# fpga.net
KiCad netlist of a schematic drawn in Altium Designer
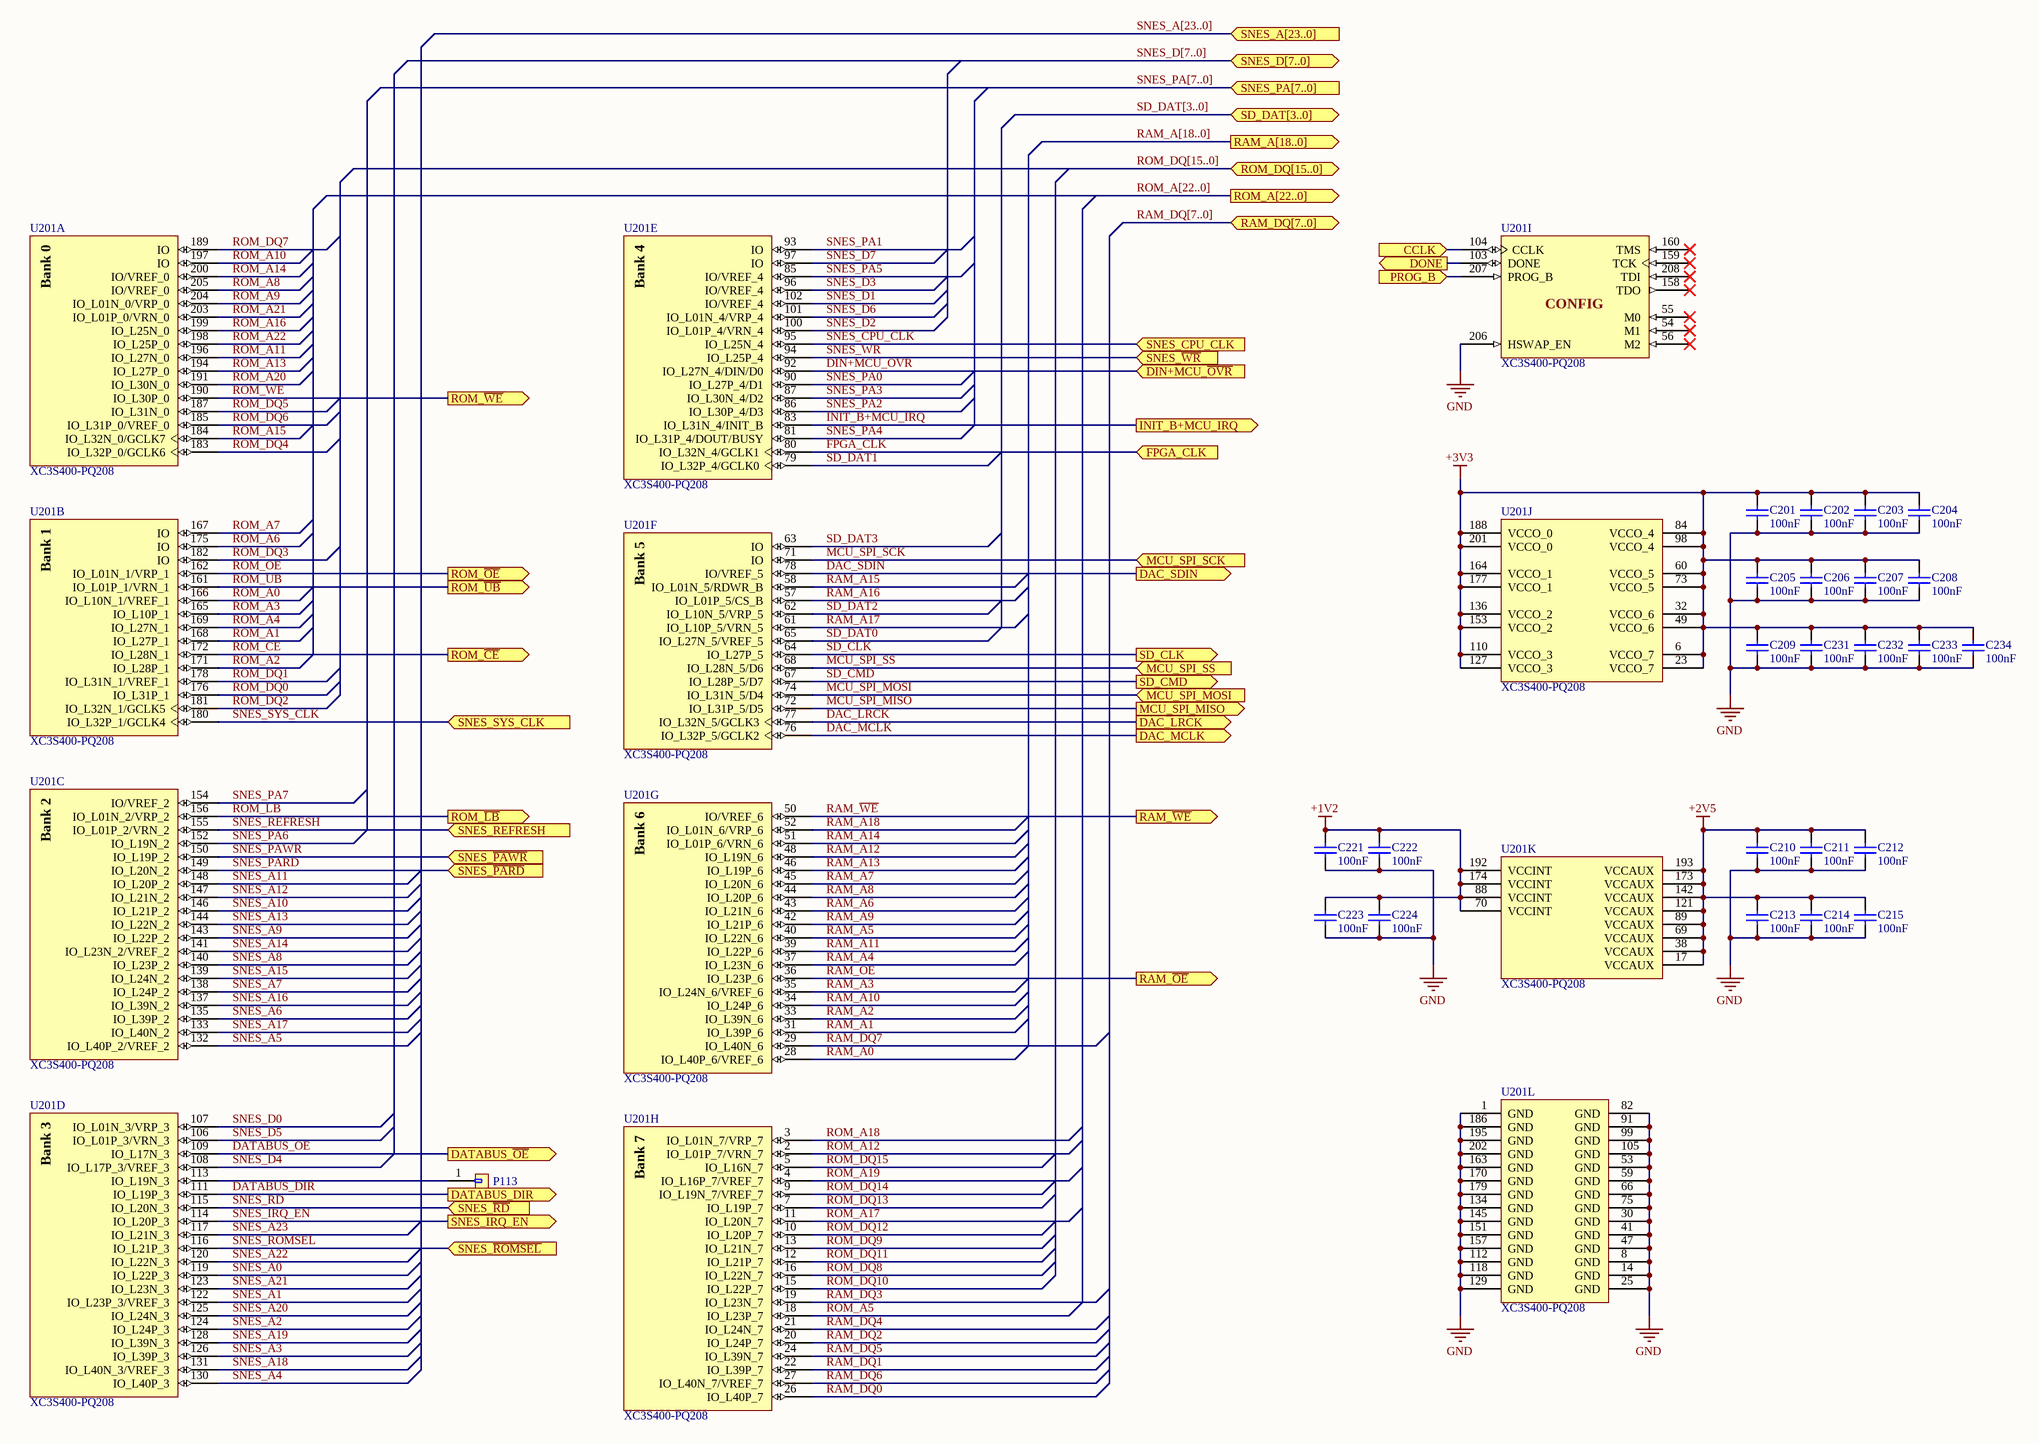
[diagram p0: fpga.SchDoc]

(export (version "E")
  (design (tool "Eeschema 10.0.6"))
  (components
    (comp (ref "C201")
      (value "100nF")
      (footprint "SM0805")
      (description "Capacitor")
      (libsource (lib "Miscellaneous Devices") (part "Cap"))
    )
    (comp (ref "C202")
      (value "100nF")
      (footprint "SM0805")
      (description "Capacitor")
      (libsource (lib "Miscellaneous Devices") (part "Cap"))
    )
    (comp (ref "C203")
      (value "100nF")
      (footprint "SM0805")
      (description "Capacitor")
      (libsource (lib "Miscellaneous Devices") (part "Cap"))
    )
    (comp (ref "C204")
      (value "100nF")
      (footprint "SM0805")
      (description "Capacitor")
      (libsource (lib "Miscellaneous Devices") (part "Cap"))
    )
    (comp (ref "C205")
      (value "100nF")
      (footprint "SM0805")
      (description "Capacitor")
      (libsource (lib "Miscellaneous Devices") (part "Cap"))
    )
    (comp (ref "C206")
      (value "100nF")
      (footprint "SM0805")
      (description "Capacitor")
      (libsource (lib "Miscellaneous Devices") (part "Cap"))
    )
    (comp (ref "C207")
      (value "100nF")
      (footprint "SM0805")
      (description "Capacitor")
      (libsource (lib "Miscellaneous Devices") (part "Cap"))
    )
    (comp (ref "C208")
      (value "100nF")
      (footprint "SM0805")
      (description "Capacitor")
      (libsource (lib "Miscellaneous Devices") (part "Cap"))
    )
    (comp (ref "C209")
      (value "100nF")
      (footprint "SM0805")
      (description "Capacitor")
      (libsource (lib "Miscellaneous Devices") (part "Cap"))
    )
    (comp (ref "C210")
      (value "100nF")
      (footprint "SM0805")
      (description "Capacitor")
      (libsource (lib "Miscellaneous Devices") (part "Cap"))
    )
    (comp (ref "C211")
      (value "100nF")
      (footprint "SM0805")
      (description "Capacitor")
      (libsource (lib "Miscellaneous Devices") (part "Cap"))
    )
    (comp (ref "C212")
      (value "100nF")
      (footprint "SM0805")
      (description "Capacitor")
      (libsource (lib "Miscellaneous Devices") (part "Cap"))
    )
    (comp (ref "C213")
      (value "100nF")
      (footprint "SM0805")
      (description "Capacitor")
      (libsource (lib "Miscellaneous Devices") (part "Cap"))
    )
    (comp (ref "C214")
      (value "100nF")
      (footprint "SM0805")
      (description "Capacitor")
      (libsource (lib "Miscellaneous Devices") (part "Cap"))
    )
    (comp (ref "C215")
      (value "100nF")
      (footprint "SM0805")
      (description "Capacitor")
      (libsource (lib "Miscellaneous Devices") (part "Cap"))
    )
    (comp (ref "C221")
      (value "100nF")
      (footprint "SM0805")
      (description "Capacitor")
      (libsource (lib "Miscellaneous Devices") (part "Cap"))
    )
    (comp (ref "C222")
      (value "100nF")
      (footprint "SM0805")
      (description "Capacitor")
      (libsource (lib "Miscellaneous Devices") (part "Cap"))
    )
    (comp (ref "C223")
      (value "100nF")
      (footprint "SM0805")
      (description "Capacitor")
      (libsource (lib "Miscellaneous Devices") (part "Cap"))
    )
    (comp (ref "C224")
      (value "100nF")
      (footprint "SM0805")
      (description "Capacitor")
      (libsource (lib "Miscellaneous Devices") (part "Cap"))
    )
    (comp (ref "C231")
      (value "100nF")
      (footprint "SM0805")
      (description "Capacitor")
      (libsource (lib "Miscellaneous Devices") (part "Cap"))
    )
    (comp (ref "C232")
      (value "100nF")
      (footprint "SM0805")
      (description "Capacitor")
      (libsource (lib "Miscellaneous Devices") (part "Cap"))
    )
    (comp (ref "C233")
      (value "100nF")
      (footprint "SM0805")
      (description "Capacitor")
      (libsource (lib "Miscellaneous Devices") (part "Cap"))
    )
    (comp (ref "C234")
      (value "100nF")
      (footprint "SM0805")
      (description "Capacitor")
      (libsource (lib "Miscellaneous Devices") (part "Cap"))
    )
    (comp (ref "P113") (value "CONN_1") (footprint "CONN_1") (libsource (lib "Schlib1") (part "CONN_1")))
    (comp (ref "U201")
      (value "XC3S400-PQ208")
      (footprint "PQFP208")
      (libsource (lib "Schlib1") (part "XC3S400-PQ208"))
    )
  )
  (nets
    (net (code "1") (name "+1V2") (class "Default")
      (node (ref "C221") (pin "1") (pinfunction "1_1") (pintype "passive"))
      (node (ref "C222") (pin "1") (pinfunction "1_1") (pintype "passive"))
      (node (ref "C223") (pin "1") (pinfunction "1_1") (pintype "passive"))
      (node (ref "C224") (pin "1") (pinfunction "1_1") (pintype "passive"))
      (node (ref "U201") (pin "174") (pinfunction "VCCINT_174") (pintype "power_in"))
      (node (ref "U201") (pin "192") (pinfunction "VCCINT_192") (pintype "power_in"))
      (node (ref "U201") (pin "70") (pinfunction "VCCINT_70") (pintype "power_in"))
      (node (ref "U201") (pin "88") (pinfunction "VCCINT_88") (pintype "power_in"))
    )
    (net (code "2") (name "+2V5") (class "Default")
      (node (ref "C210") (pin "1") (pinfunction "1_1") (pintype "passive"))
      (node (ref "C211") (pin "1") (pinfunction "1_1") (pintype "passive"))
      (node (ref "C212") (pin "1") (pinfunction "1_1") (pintype "passive"))
      (node (ref "C213") (pin "1") (pinfunction "1_1") (pintype "passive"))
      (node (ref "C214") (pin "1") (pinfunction "1_1") (pintype "passive"))
      (node (ref "C215") (pin "1") (pinfunction "1_1") (pintype "passive"))
      (node (ref "U201") (pin "121") (pinfunction "VCCAUX_121") (pintype "power_in"))
      (node (ref "U201") (pin "142") (pinfunction "VCCAUX_142") (pintype "power_in"))
      (node (ref "U201") (pin "17") (pinfunction "VCCAUX_17") (pintype "power_in"))
      (node (ref "U201") (pin "173") (pinfunction "VCCAUX_173") (pintype "power_in"))
      (node (ref "U201") (pin "193") (pinfunction "VCCAUX_193") (pintype "power_in"))
      (node (ref "U201") (pin "38") (pinfunction "VCCAUX_38") (pintype "power_in"))
      (node (ref "U201") (pin "69") (pinfunction "VCCAUX_69") (pintype "power_in"))
      (node (ref "U201") (pin "89") (pinfunction "VCCAUX_89") (pintype "power_in"))
    )
    (net (code "3") (name "+3V3") (class "Default")
      (node (ref "C201") (pin "1") (pinfunction "1_1") (pintype "passive"))
      (node (ref "C202") (pin "1") (pinfunction "1_1") (pintype "passive"))
      (node (ref "C203") (pin "1") (pinfunction "1_1") (pintype "passive"))
      (node (ref "C204") (pin "1") (pinfunction "1_1") (pintype "passive"))
      (node (ref "C205") (pin "1") (pinfunction "1_1") (pintype "passive"))
      (node (ref "C206") (pin "1") (pinfunction "1_1") (pintype "passive"))
      (node (ref "C207") (pin "1") (pinfunction "1_1") (pintype "passive"))
      (node (ref "C208") (pin "1") (pinfunction "1_1") (pintype "passive"))
      (node (ref "C209") (pin "1") (pinfunction "1_1") (pintype "passive"))
      (node (ref "C231") (pin "1") (pinfunction "1_1") (pintype "passive"))
      (node (ref "C232") (pin "1") (pinfunction "1_1") (pintype "passive"))
      (node (ref "C233") (pin "1") (pinfunction "1_1") (pintype "passive"))
      (node (ref "C234") (pin "1") (pinfunction "1_1") (pintype "passive"))
      (node (ref "U201") (pin "110") (pinfunction "VCCO_3_110") (pintype "power_in"))
      (node (ref "U201") (pin "127") (pinfunction "VCCO_3_127") (pintype "power_in"))
      (node (ref "U201") (pin "136") (pinfunction "VCCO_2_136") (pintype "power_in"))
      (node (ref "U201") (pin "153") (pinfunction "VCCO_2_153") (pintype "power_in"))
      (node (ref "U201") (pin "164") (pinfunction "VCCO_1_164") (pintype "power_in"))
      (node (ref "U201") (pin "177") (pinfunction "VCCO_1_177") (pintype "power_in"))
      (node (ref "U201") (pin "188") (pinfunction "VCCO_0_188") (pintype "power_in"))
      (node (ref "U201") (pin "201") (pinfunction "VCCO_0_201") (pintype "power_in"))
      (node (ref "U201") (pin "23") (pinfunction "VCCO_7_23") (pintype "power_in"))
      (node (ref "U201") (pin "32") (pinfunction "VCCO_6_32") (pintype "power_in"))
      (node (ref "U201") (pin "49") (pinfunction "VCCO_6_49") (pintype "power_in"))
      (node (ref "U201") (pin "6") (pinfunction "VCCO_7_6") (pintype "power_in"))
      (node (ref "U201") (pin "60") (pinfunction "VCCO_5_60") (pintype "power_in"))
      (node (ref "U201") (pin "73") (pinfunction "VCCO_5_73") (pintype "power_in"))
      (node (ref "U201") (pin "84") (pinfunction "VCCO_4_84") (pintype "power_in"))
      (node (ref "U201") (pin "98") (pinfunction "VCCO_4_98") (pintype "power_in"))
    )
    (net (code "4") (name "/CCLK") (class "Default")
      (node (ref "U201") (pin "104") (pinfunction "CCLK_104") (pintype "bidirectional"))
    )
    (net (code "5") (name "/DAC_LRCK") (class "Default")
      (node (ref "U201") (pin "77") (pinfunction "IO_L32N_5/GCLK3_77") (pintype "bidirectional"))
    )
    (net (code "6") (name "/DAC_MCLK") (class "Default")
      (node (ref "U201") (pin "76") (pinfunction "IO_L32P_5/GCLK2_76") (pintype "bidirectional"))
    )
    (net (code "7") (name "/DAC_SDIN") (class "Default")
      (node (ref "U201") (pin "78") (pinfunction "IO/VREF_5_78") (pintype "bidirectional"))
    )
    (net (code "8") (name "/DATABUS_DIR") (class "Default")
      (node (ref "U201") (pin "111") (pinfunction "IO_L19P_3_111") (pintype "bidirectional"))
    )
    (net (code "9") (name "/DATABUS_~{OE}") (class "Default")
      (node (ref "U201") (pin "109") (pinfunction "IO_L17N_3_109") (pintype "bidirectional"))
    )
    (net (code "10") (name "/DIN+MCU_~{OVR}") (class "Default")
      (node (ref "U201") (pin "92") (pinfunction "IO_L27N_4/DIN/D0_92") (pintype "bidirectional"))
    )
    (net (code "11") (name "/DONE") (class "Default")
      (node (ref "U201") (pin "103") (pinfunction "DONE_103") (pintype "bidirectional"))
    )
    (net (code "12") (name "/FPGA_CLK") (class "Default")
      (node (ref "U201") (pin "80") (pinfunction "IO_L32N_4/GCLK1_80") (pintype "bidirectional"))
    )
    (net (code "13") (name "/INIT_B+MCU_IRQ") (class "Default")
      (node (ref "U201") (pin "83") (pinfunction "IO_L31N_4/INIT_B_83") (pintype "bidirectional"))
    )
    (net (code "14") (name "/MCU_SPI_MISO") (class "Default")
      (node (ref "U201") (pin "72") (pinfunction "IO_L31P_5/D5_72") (pintype "bidirectional"))
    )
    (net (code "15") (name "/MCU_SPI_MOSI") (class "Default")
      (node (ref "U201") (pin "74") (pinfunction "IO_L31N_5/D4_74") (pintype "bidirectional"))
    )
    (net (code "16") (name "/MCU_SPI_SCK") (class "Default")
      (node (ref "U201") (pin "71") (pinfunction "IO_71") (pintype "bidirectional"))
    )
    (net (code "17") (name "/MCU_SPI_SS") (class "Default")
      (node (ref "U201") (pin "68") (pinfunction "IO_L28N_5/D6_68") (pintype "bidirectional"))
    )
    (net (code "18") (name "/PROG_B") (class "Default")
      (node (ref "U201") (pin "207") (pinfunction "PROG_B_207") (pintype "input"))
    )
    (net (code "19") (name "/RAM_A0") (class "Default")
      (node (ref "U201") (pin "28") (pinfunction "IO_L40P_6/VREF_6_28") (pintype "bidirectional"))
    )
    (net (code "20") (name "/RAM_A1") (class "Default")
      (node (ref "U201") (pin "31") (pinfunction "IO_L39P_6_31") (pintype "bidirectional"))
    )
    (net (code "21") (name "/RAM_A2") (class "Default")
      (node (ref "U201") (pin "33") (pinfunction "IO_L39N_6_33") (pintype "bidirectional"))
    )
    (net (code "22") (name "/RAM_A3") (class "Default")
      (node (ref "U201") (pin "35") (pinfunction "IO_L24N_6/VREF_6_35") (pintype "bidirectional"))
    )
    (net (code "23") (name "/RAM_A4") (class "Default")
      (node (ref "U201") (pin "37") (pinfunction "IO_L23N_6_37") (pintype "bidirectional"))
    )
    (net (code "24") (name "/RAM_A5") (class "Default")
      (node (ref "U201") (pin "40") (pinfunction "IO_L22N_6_40") (pintype "bidirectional"))
    )
    (net (code "25") (name "/RAM_A6") (class "Default")
      (node (ref "U201") (pin "43") (pinfunction "IO_L21N_6_43") (pintype "bidirectional"))
    )
    (net (code "26") (name "/RAM_A7") (class "Default")
      (node (ref "U201") (pin "45") (pinfunction "IO_L20N_6_45") (pintype "bidirectional"))
    )
    (net (code "27") (name "/RAM_A8") (class "Default")
      (node (ref "U201") (pin "44") (pinfunction "IO_L20P_6_44") (pintype "bidirectional"))
    )
    (net (code "28") (name "/RAM_A9") (class "Default")
      (node (ref "U201") (pin "42") (pinfunction "IO_L21P_6_42") (pintype "bidirectional"))
    )
    (net (code "29") (name "/RAM_A10") (class "Default")
      (node (ref "U201") (pin "34") (pinfunction "IO_L24P_6_34") (pintype "bidirectional"))
    )
    (net (code "30") (name "/RAM_A11") (class "Default")
      (node (ref "U201") (pin "39") (pinfunction "IO_L22P_6_39") (pintype "bidirectional"))
    )
    (net (code "31") (name "/RAM_A12") (class "Default")
      (node (ref "U201") (pin "48") (pinfunction "IO_L19N_6_48") (pintype "bidirectional"))
    )
    (net (code "32") (name "/RAM_A13") (class "Default")
      (node (ref "U201") (pin "46") (pinfunction "IO_L19P_6_46") (pintype "bidirectional"))
    )
    (net (code "33") (name "/RAM_A14") (class "Default")
      (node (ref "U201") (pin "51") (pinfunction "IO_L01P_6/VRN_6_51") (pintype "bidirectional"))
    )
    (net (code "34") (name "/RAM_A15") (class "Default")
      (node (ref "U201") (pin "58") (pinfunction "IO_L01N_5/RDWR_B_58") (pintype "bidirectional"))
    )
    (net (code "35") (name "/RAM_A16") (class "Default")
      (node (ref "U201") (pin "57") (pinfunction "IO_L01P_5/CS_B_57") (pintype "bidirectional"))
    )
    (net (code "36") (name "/RAM_A17") (class "Default")
      (node (ref "U201") (pin "61") (pinfunction "IO_L10P_5/VRN_5_61") (pintype "bidirectional"))
    )
    (net (code "37") (name "/RAM_A18") (class "Default")
      (node (ref "U201") (pin "52") (pinfunction "IO_L01N_6/VRP_6_52") (pintype "bidirectional"))
    )
    (net (code "39") (name "/RAM_DQ0") (class "Default")
      (node (ref "U201") (pin "26") (pinfunction "IO_L40P_7_26") (pintype "bidirectional"))
    )
    (net (code "40") (name "/RAM_DQ1") (class "Default")
      (node (ref "U201") (pin "22") (pinfunction "IO_L39P_7_22") (pintype "bidirectional"))
    )
    (net (code "41") (name "/RAM_DQ2") (class "Default")
      (node (ref "U201") (pin "20") (pinfunction "IO_L24P_7_20") (pintype "bidirectional"))
    )
    (net (code "42") (name "/RAM_DQ3") (class "Default")
      (node (ref "U201") (pin "19") (pinfunction "IO_L23N_7_19") (pintype "bidirectional"))
    )
    (net (code "43") (name "/RAM_DQ4") (class "Default")
      (node (ref "U201") (pin "21") (pinfunction "IO_L24N_7_21") (pintype "bidirectional"))
    )
    (net (code "44") (name "/RAM_DQ5") (class "Default")
      (node (ref "U201") (pin "24") (pinfunction "IO_L39N_7_24") (pintype "bidirectional"))
    )
    (net (code "45") (name "/RAM_DQ6") (class "Default")
      (node (ref "U201") (pin "27") (pinfunction "IO_L40N_7/VREF_7_27") (pintype "bidirectional"))
    )
    (net (code "46") (name "/RAM_DQ7") (class "Default")
      (node (ref "U201") (pin "29") (pinfunction "IO_L40N_6_29") (pintype "bidirectional"))
    )
    (net (code "48") (name "/RAM_~{OE}") (class "Default")
      (node (ref "U201") (pin "36") (pinfunction "IO_L23P_6_36") (pintype "bidirectional"))
    )
    (net (code "49") (name "/RAM_~{WE}") (class "Default")
      (node (ref "U201") (pin "50") (pinfunction "IO/VREF_6_50") (pintype "bidirectional"))
    )
    (net (code "50") (name "/ROM_A0") (class "Default")
      (node (ref "U201") (pin "166") (pinfunction "IO_L10N_1/VREF_1_166") (pintype "bidirectional"))
    )
    (net (code "51") (name "/ROM_A1") (class "Default")
      (node (ref "U201") (pin "168") (pinfunction "IO_L27P_1_168") (pintype "bidirectional"))
    )
    (net (code "52") (name "/ROM_A2") (class "Default")
      (node (ref "U201") (pin "171") (pinfunction "IO_L28P_1_171") (pintype "bidirectional"))
    )
    (net (code "53") (name "/ROM_A3") (class "Default")
      (node (ref "U201") (pin "165") (pinfunction "IO_L10P_1_165") (pintype "bidirectional"))
    )
    (net (code "54") (name "/ROM_A4") (class "Default")
      (node (ref "U201") (pin "169") (pinfunction "IO_L27N_1_169") (pintype "bidirectional"))
    )
    (net (code "55") (name "/ROM_A5") (class "Default")
      (node (ref "U201") (pin "18") (pinfunction "IO_L23P_7_18") (pintype "bidirectional"))
    )
    (net (code "56") (name "/ROM_A6") (class "Default")
      (node (ref "U201") (pin "175") (pinfunction "IO_175") (pintype "bidirectional"))
    )
    (net (code "57") (name "/ROM_A7") (class "Default")
      (node (ref "U201") (pin "167") (pinfunction "IO_167") (pintype "bidirectional"))
    )
    (net (code "58") (name "/ROM_A8") (class "Default")
      (node (ref "U201") (pin "205") (pinfunction "IO/VREF_0_205") (pintype "bidirectional"))
    )
    (net (code "59") (name "/ROM_A9") (class "Default")
      (node (ref "U201") (pin "204") (pinfunction "IO_L01N_0/VRP_0_204") (pintype "bidirectional"))
    )
    (net (code "60") (name "/ROM_A10") (class "Default")
      (node (ref "U201") (pin "197") (pinfunction "IO_197") (pintype "bidirectional"))
    )
    (net (code "61") (name "/ROM_A11") (class "Default")
      (node (ref "U201") (pin "196") (pinfunction "IO_L27N_0_196") (pintype "bidirectional"))
    )
    (net (code "62") (name "/ROM_A12") (class "Default")
      (node (ref "U201") (pin "2") (pinfunction "IO_L01P_7/VRN_7_2") (pintype "bidirectional"))
    )
    (net (code "63") (name "/ROM_A13") (class "Default")
      (node (ref "U201") (pin "194") (pinfunction "IO_L27P_0_194") (pintype "bidirectional"))
    )
    (net (code "64") (name "/ROM_A14") (class "Default")
      (node (ref "U201") (pin "200") (pinfunction "IO/VREF_0_200") (pintype "bidirectional"))
    )
    (net (code "65") (name "/ROM_A15") (class "Default")
      (node (ref "U201") (pin "184") (pinfunction "IO_L32N_0/GCLK7_184") (pintype "bidirectional"))
    )
    (net (code "66") (name "/ROM_A16") (class "Default")
      (node (ref "U201") (pin "199") (pinfunction "IO_L25N_0_199") (pintype "bidirectional"))
    )
    (net (code "67") (name "/ROM_A17") (class "Default")
      (node (ref "U201") (pin "11") (pinfunction "IO_L20N_7_11") (pintype "bidirectional"))
    )
    (net (code "68") (name "/ROM_A18") (class "Default")
      (node (ref "U201") (pin "3") (pinfunction "IO_L01N_7/VRP_7_3") (pintype "bidirectional"))
    )
    (net (code "69") (name "/ROM_A19") (class "Default")
      (node (ref "U201") (pin "4") (pinfunction "IO_L16P_7/VREF_7_4") (pintype "bidirectional"))
    )
    (net (code "70") (name "/ROM_A20") (class "Default")
      (node (ref "U201") (pin "191") (pinfunction "IO_L30N_0_191") (pintype "bidirectional"))
    )
    (net (code "71") (name "/ROM_A21") (class "Default")
      (node (ref "U201") (pin "203") (pinfunction "IO_L01P_0/VRN_0_203") (pintype "bidirectional"))
    )
    (net (code "72") (name "/ROM_A22") (class "Default")
      (node (ref "U201") (pin "198") (pinfunction "IO_L25P_0_198") (pintype "bidirectional"))
    )
    (net (code "74") (name "/ROM_DQ0") (class "Default")
      (node (ref "U201") (pin "176") (pinfunction "IO_L31P_1_176") (pintype "bidirectional"))
    )
    (net (code "75") (name "/ROM_DQ1") (class "Default")
      (node (ref "U201") (pin "178") (pinfunction "IO_L31N_1/VREF_1_178") (pintype "bidirectional"))
    )
    (net (code "76") (name "/ROM_DQ2") (class "Default")
      (node (ref "U201") (pin "181") (pinfunction "IO_L32N_1/GCLK5_181") (pintype "bidirectional"))
    )
    (net (code "77") (name "/ROM_DQ3") (class "Default")
      (node (ref "U201") (pin "182") (pinfunction "IO_182") (pintype "bidirectional"))
    )
    (net (code "78") (name "/ROM_DQ4") (class "Default")
      (node (ref "U201") (pin "183") (pinfunction "IO_L32P_0/GCLK6_183") (pintype "bidirectional"))
    )
    (net (code "79") (name "/ROM_DQ5") (class "Default")
      (node (ref "U201") (pin "187") (pinfunction "IO_L31N_0_187") (pintype "bidirectional"))
    )
    (net (code "80") (name "/ROM_DQ6") (class "Default")
      (node (ref "U201") (pin "185") (pinfunction "IO_L31P_0/VREF_0_185") (pintype "bidirectional"))
    )
    (net (code "81") (name "/ROM_DQ7") (class "Default")
      (node (ref "U201") (pin "189") (pinfunction "IO_189") (pintype "bidirectional"))
    )
    (net (code "82") (name "/ROM_DQ8") (class "Default")
      (node (ref "U201") (pin "16") (pinfunction "IO_L22N_7_16") (pintype "bidirectional"))
    )
    (net (code "83") (name "/ROM_DQ9") (class "Default")
      (node (ref "U201") (pin "13") (pinfunction "IO_L21N_7_13") (pintype "bidirectional"))
    )
    (net (code "84") (name "/ROM_DQ10") (class "Default")
      (node (ref "U201") (pin "15") (pinfunction "IO_L22P_7_15") (pintype "bidirectional"))
    )
    (net (code "85") (name "/ROM_DQ11") (class "Default")
      (node (ref "U201") (pin "12") (pinfunction "IO_L21P_7_12") (pintype "bidirectional"))
    )
    (net (code "86") (name "/ROM_DQ12") (class "Default")
      (node (ref "U201") (pin "10") (pinfunction "IO_L20P_7_10") (pintype "bidirectional"))
    )
    (net (code "87") (name "/ROM_DQ13") (class "Default")
      (node (ref "U201") (pin "7") (pinfunction "IO_L19P_7_7") (pintype "bidirectional"))
    )
    (net (code "88") (name "/ROM_DQ14") (class "Default")
      (node (ref "U201") (pin "9") (pinfunction "IO_L19N_7/VREF_7_9") (pintype "bidirectional"))
    )
    (net (code "89") (name "/ROM_DQ15") (class "Default")
      (node (ref "U201") (pin "5") (pinfunction "IO_L16N_7_5") (pintype "bidirectional"))
    )
    (net (code "91") (name "/ROM_~{CE}") (class "Default")
      (node (ref "U201") (pin "172") (pinfunction "IO_L28N_1_172") (pintype "bidirectional"))
    )
    (net (code "92") (name "/ROM_~{LB}") (class "Default")
      (node (ref "U201") (pin "156") (pinfunction "IO_L01N_2/VRP_2_156") (pintype "bidirectional"))
    )
    (net (code "93") (name "/ROM_~{OE}") (class "Default")
      (node (ref "U201") (pin "162") (pinfunction "IO_L01N_1/VRP_1_162") (pintype "bidirectional"))
    )
    (net (code "94") (name "/ROM_~{UB}") (class "Default")
      (node (ref "U201") (pin "161") (pinfunction "IO_L01P_1/VRN_1_161") (pintype "bidirectional"))
    )
    (net (code "95") (name "/ROM_~{WE}") (class "Default")
      (node (ref "U201") (pin "190") (pinfunction "IO_L30P_0_190") (pintype "bidirectional"))
    )
    (net (code "96") (name "/SD_CLK") (class "Default")
      (node (ref "U201") (pin "64") (pinfunction "IO_L27P_5_64") (pintype "bidirectional"))
    )
    (net (code "97") (name "/SD_CMD") (class "Default")
      (node (ref "U201") (pin "67") (pinfunction "IO_L28P_5/D7_67") (pintype "bidirectional"))
    )
    (net (code "98") (name "/SD_DAT0") (class "Default")
      (node (ref "U201") (pin "65") (pinfunction "IO_L27N_5/VREF_5_65") (pintype "bidirectional"))
    )
    (net (code "99") (name "/SD_DAT1") (class "Default")
      (node (ref "U201") (pin "79") (pinfunction "IO_L32P_4/GCLK0_79") (pintype "bidirectional"))
    )
    (net (code "100") (name "/SD_DAT2") (class "Default")
      (node (ref "U201") (pin "62") (pinfunction "IO_L10N_5/VRP_5_62") (pintype "bidirectional"))
    )
    (net (code "101") (name "/SD_DAT3") (class "Default")
      (node (ref "U201") (pin "63") (pinfunction "IO_63") (pintype "bidirectional"))
    )
    (net (code "103") (name "/SNES_A0") (class "Default")
      (node (ref "U201") (pin "119") (pinfunction "IO_L22P_3_119") (pintype "bidirectional"))
    )
    (net (code "104") (name "/SNES_A1") (class "Default")
      (node (ref "U201") (pin "122") (pinfunction "IO_L23P_3/VREF_3_122") (pintype "bidirectional"))
    )
    (net (code "105") (name "/SNES_A2") (class "Default")
      (node (ref "U201") (pin "124") (pinfunction "IO_L24P_3_124") (pintype "bidirectional"))
    )
    (net (code "106") (name "/SNES_A3") (class "Default")
      (node (ref "U201") (pin "126") (pinfunction "IO_L39P_3_126") (pintype "bidirectional"))
    )
    (net (code "107") (name "/SNES_A4") (class "Default")
      (node (ref "U201") (pin "130") (pinfunction "IO_L40P_3_130") (pintype "bidirectional"))
    )
    (net (code "108") (name "/SNES_A5") (class "Default")
      (node (ref "U201") (pin "132") (pinfunction "IO_L40P_2/VREF_2_132") (pintype "bidirectional"))
    )
    (net (code "109") (name "/SNES_A6") (class "Default")
      (node (ref "U201") (pin "135") (pinfunction "IO_L39P_2_135") (pintype "bidirectional"))
    )
    (net (code "110") (name "/SNES_A7") (class "Default")
      (node (ref "U201") (pin "138") (pinfunction "IO_L24P_2_138") (pintype "bidirectional"))
    )
    (net (code "111") (name "/SNES_A8") (class "Default")
      (node (ref "U201") (pin "140") (pinfunction "IO_L23P_2_140") (pintype "bidirectional"))
    )
    (net (code "112") (name "/SNES_A9") (class "Default")
      (node (ref "U201") (pin "143") (pinfunction "IO_L22P_2_143") (pintype "bidirectional"))
    )
    (net (code "113") (name "/SNES_A10") (class "Default")
      (node (ref "U201") (pin "146") (pinfunction "IO_L21P_2_146") (pintype "bidirectional"))
    )
    (net (code "114") (name "/SNES_A11") (class "Default")
      (node (ref "U201") (pin "148") (pinfunction "IO_L20P_2_148") (pintype "bidirectional"))
    )
    (net (code "115") (name "/SNES_A12") (class "Default")
      (node (ref "U201") (pin "147") (pinfunction "IO_L21N_2_147") (pintype "bidirectional"))
    )
    (net (code "116") (name "/SNES_A13") (class "Default")
      (node (ref "U201") (pin "144") (pinfunction "IO_L22N_2_144") (pintype "bidirectional"))
    )
    (net (code "117") (name "/SNES_A14") (class "Default")
      (node (ref "U201") (pin "141") (pinfunction "IO_L23N_2/VREF_2_141") (pintype "bidirectional"))
    )
    (net (code "118") (name "/SNES_A15") (class "Default")
      (node (ref "U201") (pin "139") (pinfunction "IO_L24N_2_139") (pintype "bidirectional"))
    )
    (net (code "119") (name "/SNES_A16") (class "Default")
      (node (ref "U201") (pin "137") (pinfunction "IO_L39N_2_137") (pintype "bidirectional"))
    )
    (net (code "120") (name "/SNES_A17") (class "Default")
      (node (ref "U201") (pin "133") (pinfunction "IO_L40N_2_133") (pintype "bidirectional"))
    )
    (net (code "121") (name "/SNES_A18") (class "Default")
      (node (ref "U201") (pin "131") (pinfunction "IO_L40N_3/VREF_3_131") (pintype "bidirectional"))
    )
    (net (code "122") (name "/SNES_A19") (class "Default")
      (node (ref "U201") (pin "128") (pinfunction "IO_L39N_3_128") (pintype "bidirectional"))
    )
    (net (code "123") (name "/SNES_A20") (class "Default")
      (node (ref "U201") (pin "125") (pinfunction "IO_L24N_3_125") (pintype "bidirectional"))
    )
    (net (code "124") (name "/SNES_A21") (class "Default")
      (node (ref "U201") (pin "123") (pinfunction "IO_L23N_3_123") (pintype "bidirectional"))
    )
    (net (code "125") (name "/SNES_A22") (class "Default")
      (node (ref "U201") (pin "120") (pinfunction "IO_L22N_3_120") (pintype "bidirectional"))
    )
    (net (code "126") (name "/SNES_A23") (class "Default")
      (node (ref "U201") (pin "117") (pinfunction "IO_L21N_3_117") (pintype "bidirectional"))
    )
    (net (code "128") (name "/SNES_CPU_CLK") (class "Default")
      (node (ref "U201") (pin "95") (pinfunction "IO_L25N_4_95") (pintype "bidirectional"))
    )
    (net (code "129") (name "/SNES_D0") (class "Default")
      (node (ref "U201") (pin "107") (pinfunction "IO_L01N_3/VRP_3_107") (pintype "bidirectional"))
    )
    (net (code "130") (name "/SNES_D1") (class "Default")
      (node (ref "U201") (pin "102") (pinfunction "IO/VREF_4_102") (pintype "bidirectional"))
    )
    (net (code "131") (name "/SNES_D2") (class "Default")
      (node (ref "U201") (pin "100") (pinfunction "IO_L01P_4/VRN_4_100") (pintype "bidirectional"))
    )
    (net (code "132") (name "/SNES_D3") (class "Default")
      (node (ref "U201") (pin "96") (pinfunction "IO/VREF_4_96") (pintype "bidirectional"))
    )
    (net (code "133") (name "/SNES_D4") (class "Default")
      (node (ref "U201") (pin "108") (pinfunction "IO_L17P_3/VREF_3_108") (pintype "bidirectional"))
    )
    (net (code "134") (name "/SNES_D5") (class "Default")
      (node (ref "U201") (pin "106") (pinfunction "IO_L01P_3/VRN_3_106") (pintype "bidirectional"))
    )
    (net (code "135") (name "/SNES_D6") (class "Default")
      (node (ref "U201") (pin "101") (pinfunction "IO_L01N_4/VRP_4_101") (pintype "bidirectional"))
    )
    (net (code "136") (name "/SNES_D7") (class "Default")
      (node (ref "U201") (pin "97") (pinfunction "IO_97") (pintype "bidirectional"))
    )
    (net (code "138") (name "/SNES_IRQ_EN") (class "Default")
      (node (ref "U201") (pin "114") (pinfunction "IO_L20P_3_114") (pintype "bidirectional"))
    )
    (net (code "139") (name "/SNES_PA0") (class "Default")
      (node (ref "U201") (pin "90") (pinfunction "IO_L27P_4/D1_90") (pintype "bidirectional"))
    )
    (net (code "140") (name "/SNES_PA1") (class "Default")
      (node (ref "U201") (pin "93") (pinfunction "IO_93") (pintype "bidirectional"))
    )
    (net (code "141") (name "/SNES_PA2") (class "Default")
      (node (ref "U201") (pin "86") (pinfunction "IO_L30P_4/D3_86") (pintype "bidirectional"))
    )
    (net (code "142") (name "/SNES_PA3") (class "Default")
      (node (ref "U201") (pin "87") (pinfunction "IO_L30N_4/D2_87") (pintype "bidirectional"))
    )
    (net (code "143") (name "/SNES_PA4") (class "Default")
      (node (ref "U201") (pin "81") (pinfunction "IO_L31P_4/DOUT/BUSY_81") (pintype "bidirectional"))
    )
    (net (code "144") (name "/SNES_PA5") (class "Default")
      (node (ref "U201") (pin "85") (pinfunction "IO/VREF_4_85") (pintype "bidirectional"))
    )
    (net (code "145") (name "/SNES_PA6") (class "Default")
      (node (ref "U201") (pin "152") (pinfunction "IO_L19N_2_152") (pintype "bidirectional"))
    )
    (net (code "146") (name "/SNES_PA7") (class "Default")
      (node (ref "U201") (pin "154") (pinfunction "IO/VREF_2_154") (pintype "bidirectional"))
    )
    (net (code "148") (name "/SNES_REFRESH") (class "Default")
      (node (ref "U201") (pin "155") (pinfunction "IO_L01P_2/VRN_2_155") (pintype "bidirectional"))
    )
    (net (code "149") (name "/SNES_SYS_CLK") (class "Default")
      (node (ref "U201") (pin "180") (pinfunction "IO_L32P_1/GCLK4_180") (pintype "bidirectional"))
    )
    (net (code "150") (name "/SNES_~{PARD}") (class "Default")
      (node (ref "U201") (pin "149") (pinfunction "IO_L20N_2_149") (pintype "bidirectional"))
    )
    (net (code "151") (name "/SNES_~{PAWR}") (class "Default")
      (node (ref "U201") (pin "150") (pinfunction "IO_L19P_2_150") (pintype "bidirectional"))
    )
    (net (code "152") (name "/SNES_~{RD}") (class "Default")
      (node (ref "U201") (pin "115") (pinfunction "IO_L20N_3_115") (pintype "bidirectional"))
    )
    (net (code "153") (name "/SNES_~{ROMSEL}") (class "Default")
      (node (ref "U201") (pin "116") (pinfunction "IO_L21P_3_116") (pintype "bidirectional"))
    )
    (net (code "154") (name "/SNES_~{WR}") (class "Default")
      (node (ref "U201") (pin "94") (pinfunction "IO_L25P_4_94") (pintype "bidirectional"))
    )
    (net (code "155") (name "GND") (class "Default")
      (node (ref "C201") (pin "2") (pinfunction "2_2") (pintype "passive"))
      (node (ref "C202") (pin "2") (pinfunction "2_2") (pintype "passive"))
      (node (ref "C203") (pin "2") (pinfunction "2_2") (pintype "passive"))
      (node (ref "C204") (pin "2") (pinfunction "2_2") (pintype "passive"))
      (node (ref "C205") (pin "2") (pinfunction "2_2") (pintype "passive"))
      (node (ref "C206") (pin "2") (pinfunction "2_2") (pintype "passive"))
      (node (ref "C207") (pin "2") (pinfunction "2_2") (pintype "passive"))
      (node (ref "C208") (pin "2") (pinfunction "2_2") (pintype "passive"))
      (node (ref "C209") (pin "2") (pinfunction "2_2") (pintype "passive"))
      (node (ref "C210") (pin "2") (pinfunction "2_2") (pintype "passive"))
      (node (ref "C211") (pin "2") (pinfunction "2_2") (pintype "passive"))
      (node (ref "C212") (pin "2") (pinfunction "2_2") (pintype "passive"))
      (node (ref "C213") (pin "2") (pinfunction "2_2") (pintype "passive"))
      (node (ref "C214") (pin "2") (pinfunction "2_2") (pintype "passive"))
      (node (ref "C215") (pin "2") (pinfunction "2_2") (pintype "passive"))
      (node (ref "C221") (pin "2") (pinfunction "2_2") (pintype "passive"))
      (node (ref "C222") (pin "2") (pinfunction "2_2") (pintype "passive"))
      (node (ref "C223") (pin "2") (pinfunction "2_2") (pintype "passive"))
      (node (ref "C224") (pin "2") (pinfunction "2_2") (pintype "passive"))
      (node (ref "C231") (pin "2") (pinfunction "2_2") (pintype "passive"))
      (node (ref "C232") (pin "2") (pinfunction "2_2") (pintype "passive"))
      (node (ref "C233") (pin "2") (pinfunction "2_2") (pintype "passive"))
      (node (ref "C234") (pin "2") (pinfunction "2_2") (pintype "passive"))
      (node (ref "U201") (pin "1") (pinfunction "GND_1") (pintype "power_in"))
      (node (ref "U201") (pin "105") (pinfunction "GND_105") (pintype "power_in"))
      (node (ref "U201") (pin "112") (pinfunction "GND_112") (pintype "power_in"))
      (node (ref "U201") (pin "118") (pinfunction "GND_118") (pintype "power_in"))
      (node (ref "U201") (pin "129") (pinfunction "GND_129") (pintype "power_in"))
      (node (ref "U201") (pin "134") (pinfunction "GND_134") (pintype "power_in"))
      (node (ref "U201") (pin "14") (pinfunction "GND_14") (pintype "power_in"))
      (node (ref "U201") (pin "145") (pinfunction "GND_145") (pintype "power_in"))
      (node (ref "U201") (pin "151") (pinfunction "GND_151") (pintype "power_in"))
      (node (ref "U201") (pin "157") (pinfunction "GND_157") (pintype "power_in"))
      (node (ref "U201") (pin "163") (pinfunction "GND_163") (pintype "power_in"))
      (node (ref "U201") (pin "170") (pinfunction "GND_170") (pintype "power_in"))
      (node (ref "U201") (pin "179") (pinfunction "GND_179") (pintype "power_in"))
      (node (ref "U201") (pin "186") (pinfunction "GND_186") (pintype "power_in"))
      (node (ref "U201") (pin "195") (pinfunction "GND_195") (pintype "power_in"))
      (node (ref "U201") (pin "202") (pinfunction "GND_202") (pintype "power_in"))
      (node (ref "U201") (pin "206") (pinfunction "HSWAP_EN_206") (pintype "input"))
      (node (ref "U201") (pin "25") (pinfunction "GND_25") (pintype "power_in"))
      (node (ref "U201") (pin "30") (pinfunction "GND_30") (pintype "power_in"))
      (node (ref "U201") (pin "41") (pinfunction "GND_41") (pintype "power_in"))
      (node (ref "U201") (pin "47") (pinfunction "GND_47") (pintype "power_in"))
      (node (ref "U201") (pin "53") (pinfunction "GND_53") (pintype "power_in"))
      (node (ref "U201") (pin "59") (pinfunction "GND_59") (pintype "power_in"))
      (node (ref "U201") (pin "66") (pinfunction "GND_66") (pintype "power_in"))
      (node (ref "U201") (pin "75") (pinfunction "GND_75") (pintype "power_in"))
      (node (ref "U201") (pin "8") (pinfunction "GND_8") (pintype "power_in"))
      (node (ref "U201") (pin "82") (pinfunction "GND_82") (pintype "power_in"))
      (node (ref "U201") (pin "91") (pinfunction "GND_91") (pintype "power_in"))
      (node (ref "U201") (pin "99") (pinfunction "GND_99") (pintype "power_in"))
    )
    (net (code "156") (name "Net-(U201D-IO_L19N_3)") (class "Default")
      (node (ref "P113") (pin "1") (pinfunction "1_1") (pintype "passive"))
      (node (ref "U201") (pin "113") (pinfunction "IO_L19N_3_113") (pintype "bidirectional"))
    )
    (net (code "157") (name "unconnected-(U201I-M0-Pad55)") (class "Default")
      (node (ref "U201") (pin "55") (pinfunction "M0_55") (pintype "input+no_connect"))
    )
    (net (code "158") (name "unconnected-(U201I-M1-Pad54)") (class "Default")
      (node (ref "U201") (pin "54") (pinfunction "M1_54") (pintype "input+no_connect"))
    )
    (net (code "159") (name "unconnected-(U201I-M2-Pad56)") (class "Default")
      (node (ref "U201") (pin "56") (pinfunction "M2_56") (pintype "input+no_connect"))
    )
    (net (code "160") (name "unconnected-(U201I-TCK-Pad159)") (class "Default")
      (node (ref "U201") (pin "159") (pinfunction "TCK_159") (pintype "input+no_connect"))
    )
    (net (code "161") (name "unconnected-(U201I-TDI-Pad208)") (class "Default")
      (node (ref "U201") (pin "208") (pinfunction "TDI_208") (pintype "input+no_connect"))
    )
    (net (code "162") (name "unconnected-(U201I-TDO-Pad158)") (class "Default")
      (node (ref "U201") (pin "158") (pinfunction "TDO_158") (pintype "output+no_connect"))
    )
    (net (code "163") (name "unconnected-(U201I-TMS-Pad160)") (class "Default")
      (node (ref "U201") (pin "160") (pinfunction "TMS_160") (pintype "input+no_connect"))
    )
  )
)
